# Power.net
KiCad netlist of a schematic drawn in Altium Designer
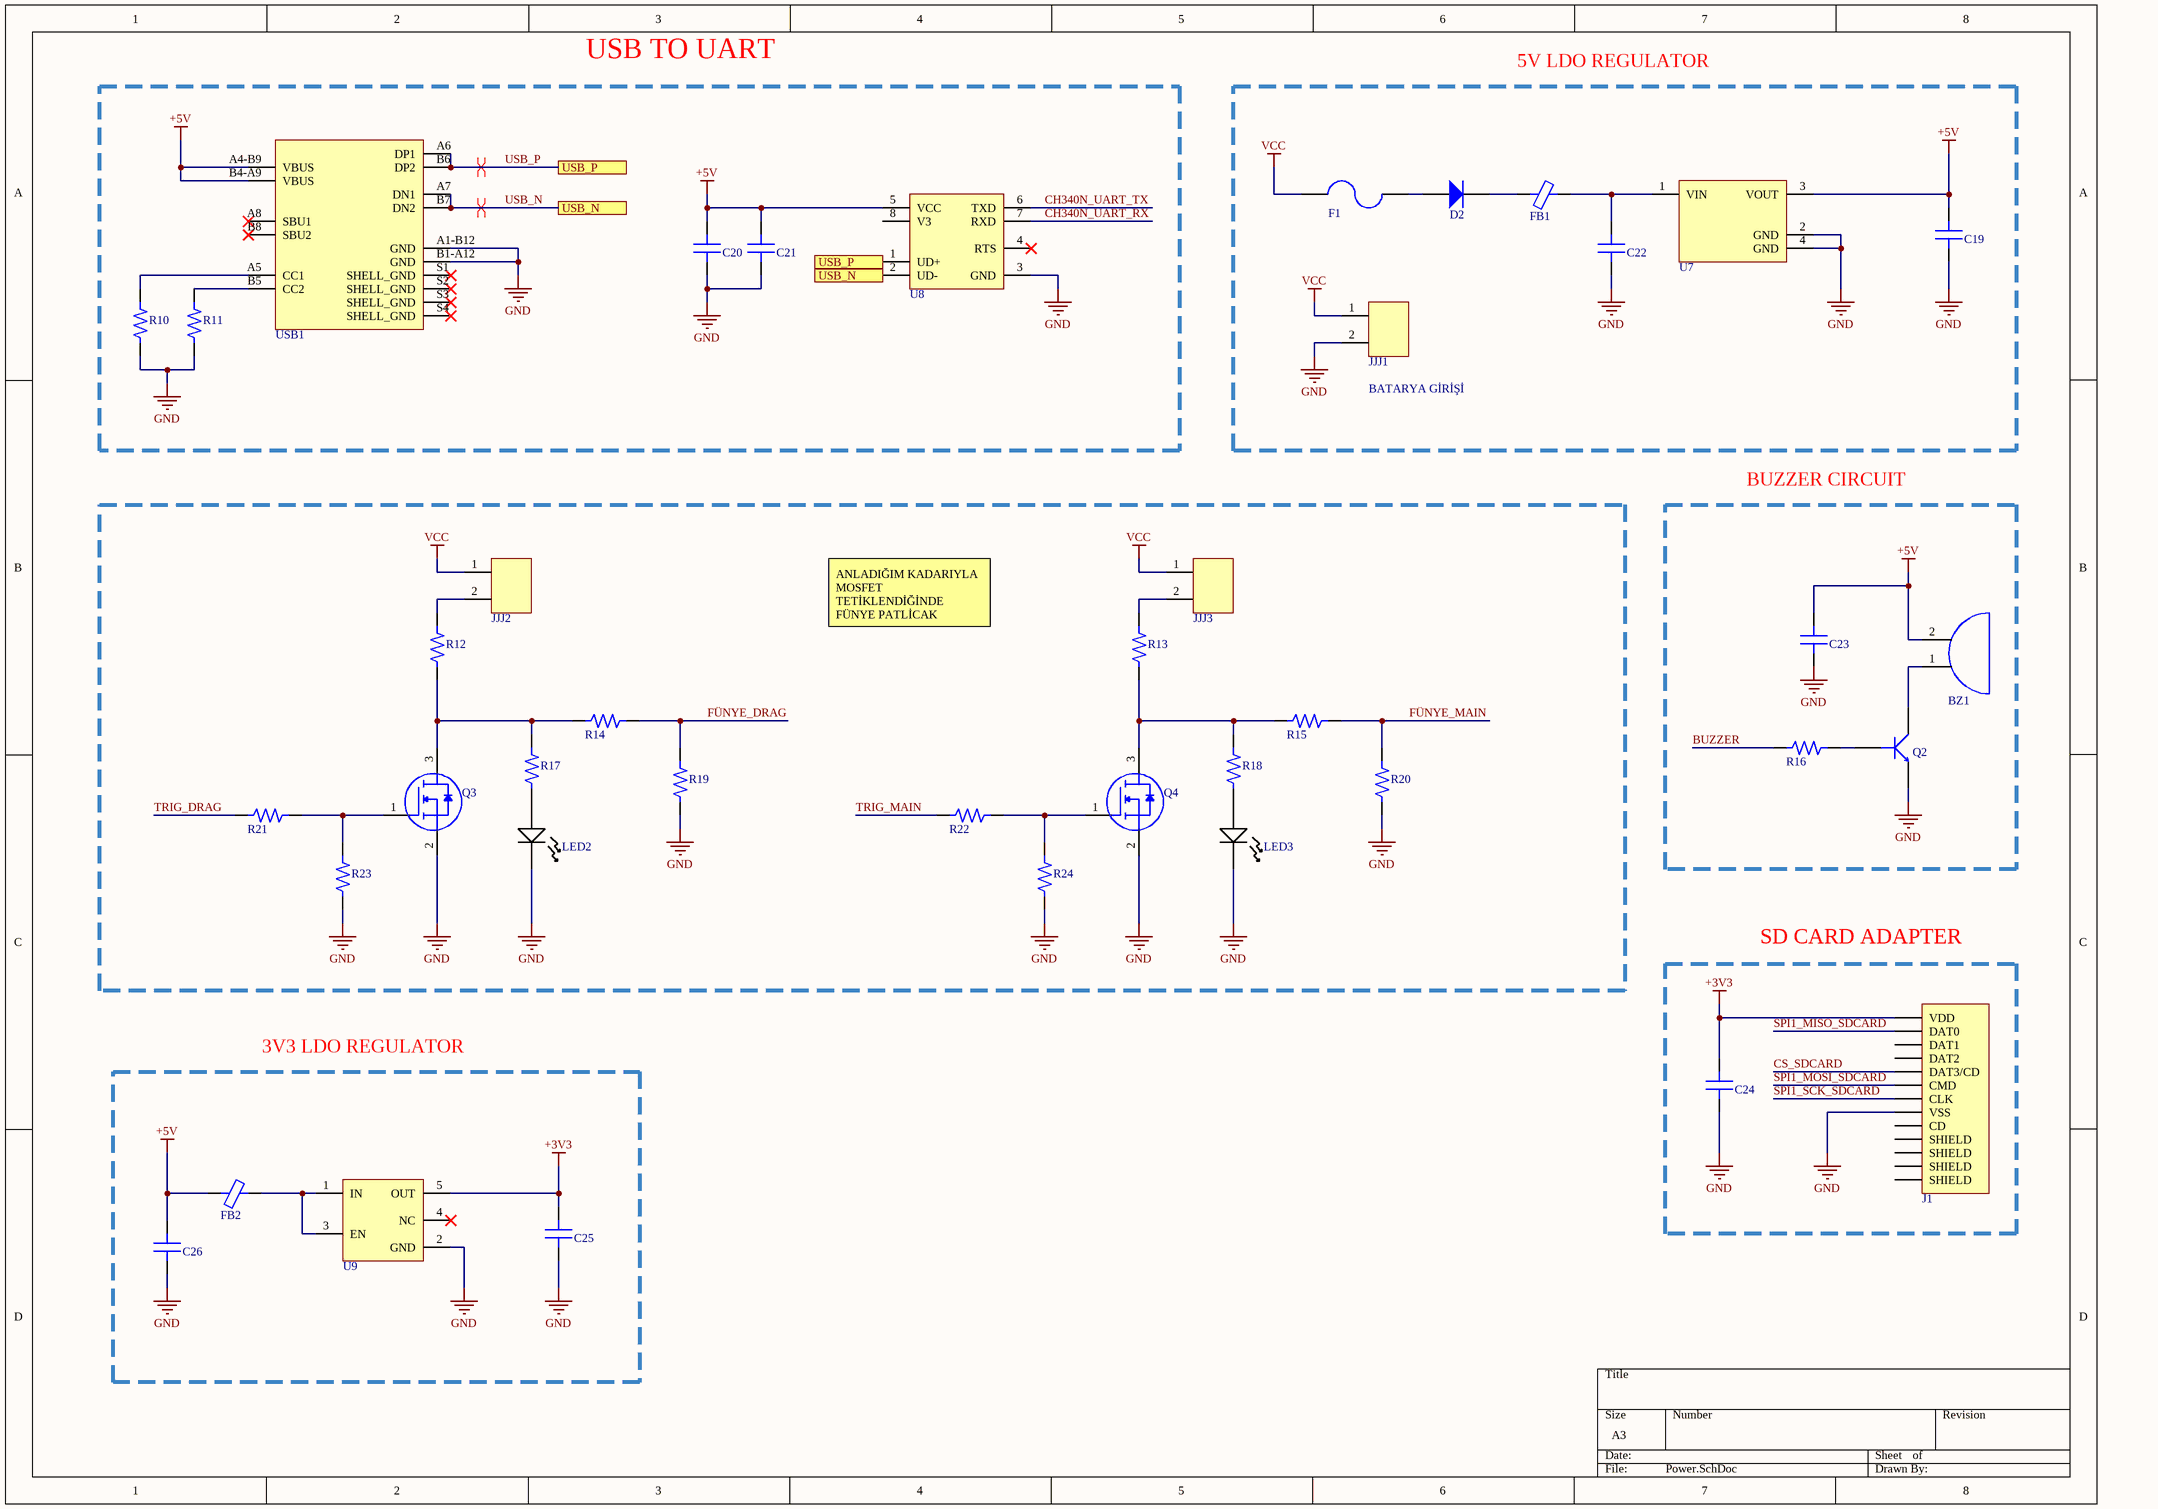
[diagram p0: Power.SchDoc]

(export (version "E")
  (design (tool "Eeschema 10.0.6"))
  (components
    (comp (ref "BZ1")
      (value "CMI-9605IC-0580T")
      (footprint "BUZZER")
      (description "Audio Buzzer Magnetic 3VDC 7VDC 30mA 5VDC 85dB 2600Hz to 2800Hz Through Hole Pin Box")
      (fields (field (name "MANUFACTURER") "CUI Devices"))
      (libsource (lib "ROKET_LIBRARY") (part "BUZZER"))
    )
    (comp (ref "C19")
      (value "CAP CER 10uF 0805")
      (footprint "CAP_0805")
      (libsource (lib "ROKET_LIBRARY") (part "CAP CER 10uF 0805"))
    )
    (comp (ref "C20")
      (value "CAP CER 100nF 0805")
      (footprint "CAP_0805")
      (libsource (lib "ROKET_LIBRARY") (part "CAP CER 100nF 0805"))
    )
    (comp (ref "C21")
      (value "CAP CER 100nF 0805")
      (footprint "CAP_0805")
      (libsource (lib "ROKET_LIBRARY") (part "CAP CER 100nF 0805"))
    )
    (comp (ref "C22")
      (value "CAP CER 10uF 0805")
      (footprint "CAP_0805")
      (libsource (lib "ROKET_LIBRARY") (part "CAP CER 10uF 0805"))
    )
    (comp (ref "C23")
      (value "CAP CER 100nF 0805")
      (footprint "CAP_0805")
      (libsource (lib "ROKET_LIBRARY") (part "CAP CER 100nF 0805"))
    )
    (comp (ref "C24")
      (value "CAP CER 100nF 0805")
      (footprint "CAP_0805")
      (libsource (lib "ROKET_LIBRARY") (part "CAP CER 100nF 0805"))
    )
    (comp (ref "C25")
      (value "CAP CER 1uF 0805")
      (footprint "CAP_0805")
      (libsource (lib "ROKET_LIBRARY") (part "CAP CER 1uF 0805"))
    )
    (comp (ref "C26")
      (value "CAP CER 1uF 0805")
      (footprint "CAP_0805")
      (libsource (lib "ROKET_LIBRARY") (part "CAP CER 1uF 0805"))
    )
    (comp (ref "D2")
      (value "DIODE GEN PURP 75V 150MA SOD323F")
      (footprint "SOD323F")
      (description "VR=75V IF=150mA Trr=4ns P=200mW")
      (fields
        (field (name "MANUFACTURER") "ON Semiconductor / Fairchild")
        (field (name "MANUFACTURER PART NUMBER") "1N4148WS")
      )
      (libsource (lib "ROKET_LIBRARY") (part "DIODE"))
    )
    (comp (ref "F1")
      (value "FUSE 3413.0216.22")
      (footprint "FUSE_1206")
      (description "Fuse Chip Fast Acting 1A 32V SMD Solder Pad 1206 Glass T/R VDE/cULus")
      (fields
        (field (name "MANUFACTURER") "Schurter")
        (field (name "MANUFACTURER PART NUMBER") "3413.0216.22")
      )
      (libsource (lib "ROKET_LIBRARY") (part "FUSE"))
    )
    (comp (ref "FB1")
      (value "MPZ2012S601AT000")
      (footprint "FERRITE BEAD_0805")
      (description "0805 600Ω ±25% DCR=0.1Ω 2A")
      (fields (field (name "MANUFACTURER") "TDK"))
      (libsource (lib "ROKET_LIBRARY") (part "FERRITE BEAD"))
    )
    (comp (ref "FB2")
      (value "MPZ2012S601AT000")
      (footprint "FERRITE BEAD_0805")
      (description "0805 600Ω ±25% DCR=0.1Ω 2A")
      (fields (field (name "MANUFACTURER") "TDK"))
      (libsource (lib "ROKET_LIBRARY") (part "FERRITE BEAD"))
    )
    (comp (ref "J1")
      (value "MEM2075-00-140-01-A")
      (footprint "SD CARD")
      (description "MEM2075 Series Normally Open SMT Push-Push MicroSD Memory Card Connector")
      (fields (field (name "MANUFACTURER") "Global Connector Technology"))
      (libsource (lib "ROKET_LIBRARY") (part "SD CARD"))
    )
    (comp (ref "JJJ1")
      (value "HEADER x2")
      (footprint "HEADER x2")
      (description "Conn Screw Type Terminal Block 2 POS 3.5mm Solder ST Thru-Hole 10A")
      (fields
        (field (name "MANUFACTURER") "On-Shore Technology")
        (field (name "MANUFACTURER PART NUMBER") "OSTTE020104")
      )
      (libsource (lib "Roket_Library") (part "HEADER x2"))
    )
    (comp (ref "JJJ2")
      (value "HEADER x2")
      (footprint "HEADER x2")
      (description "Conn Screw Type Terminal Block 2 POS 3.5mm Solder ST Thru-Hole 10A")
      (fields
        (field (name "MANUFACTURER") "On-Shore Technology")
        (field (name "MANUFACTURER PART NUMBER") "OSTTE020104")
      )
      (libsource (lib "Roket_Library") (part "HEADER x2"))
    )
    (comp (ref "JJJ3")
      (value "HEADER x2")
      (footprint "HEADER x2")
      (description "Conn Screw Type Terminal Block 2 POS 3.5mm Solder ST Thru-Hole 10A")
      (fields
        (field (name "MANUFACTURER") "On-Shore Technology")
        (field (name "MANUFACTURER PART NUMBER") "OSTTE020104")
      )
      (libsource (lib "Roket_Library") (part "HEADER x2"))
    )
    (comp (ref "LED2")
      (value "CMD17-21VRD/TR8")
      (footprint "LED RED_0805")
      (description "LED Uni-Color Red 640nm 2-Pin SMT T/R")
      (fields (field (name "MANUFACTURER") "VCC CHML"))
      (libsource (lib "ROKET_LIBRARY") (part "LED RED"))
    )
    (comp (ref "LED3")
      (value "CMD17-21VRD/TR8")
      (footprint "LED RED_0805")
      (description "LED Uni-Color Red 640nm 2-Pin SMT T/R")
      (fields (field (name "MANUFACTURER") "VCC CHML"))
      (libsource (lib "ROKET_LIBRARY") (part "LED RED"))
    )
    (comp (ref "Q2")
      (value "MMBT3904-7-F")
      (footprint "SOT_23F")
      (description "NPN Ic=200mA Vceo=40V hfe=100~300 fT=310MHz P=300mW SOT-23")
      (fields (field (name "MANUFACTURER") "Diodes Zetex"))
      (libsource (lib "ROKET_LIBRARY") (part "BJT_NPN"))
    )
    (comp (ref "Q3")
      (value "NTR5103NT1G")
      (footprint "SOT-23-3")
      (description "MOSFET N-CH 60V 0.26A SOT23")
      (fields (field (name "MANUFACTURER") "ON Semiconductor"))
      (libsource (lib "ROKET_LIBRARY") (part "MOSFET N-Channel"))
    )
    (comp (ref "Q4")
      (value "NTR5103NT1G")
      (footprint "SOT-23-3")
      (description "MOSFET N-CH 60V 0.26A SOT23")
      (fields (field (name "MANUFACTURER") "ON Semiconductor"))
      (libsource (lib "ROKET_LIBRARY") (part "MOSFET N-Channel"))
    )
    (comp (ref "R10")
      (value "RES 10K OHM 0805")
      (footprint "RES_0805")
      (libsource (lib "ROKET_LIBRARY") (part "RES 10K OHM 0805"))
    )
    (comp (ref "R11")
      (value "RES 10K OHM 0805")
      (footprint "RES_0805")
      (libsource (lib "ROKET_LIBRARY") (part "RES 10K OHM 0805"))
    )
    (comp (ref "R12")
      (value "RES 0 OHM 0805")
      (footprint "RES_0805")
      (libsource (lib "ROKET_LIBRARY") (part "RES 0 OHM 0805"))
    )
    (comp (ref "R13")
      (value "RES 0 OHM 0805")
      (footprint "RES_0805")
      (libsource (lib "ROKET_LIBRARY") (part "RES 0 OHM 0805"))
    )
    (comp (ref "R14")
      (value "RES 20K OHM 0805")
      (footprint "RES_0805")
      (libsource (lib "ROKET_LIBRARY") (part "RES 20K OHM 0805"))
    )
    (comp (ref "R15")
      (value "RES 20K OHM 0805")
      (footprint "RES_0805")
      (libsource (lib "ROKET_LIBRARY") (part "RES 20K OHM 0805"))
    )
    (comp (ref "R16")
      (value "RES 100 OHM 0805")
      (footprint "RES_0805")
      (libsource (lib "ROKET_LIBRARY") (part "RES 100 OHM 0805"))
    )
    (comp (ref "R17")
      (value "RES 470 OHM 0805")
      (footprint "RES_0805")
      (libsource (lib "ROKET_LIBRARY") (part "RES 470 OHM 0805"))
    )
    (comp (ref "R18")
      (value "RES 470 OHM 0805")
      (footprint "RES_0805")
      (libsource (lib "ROKET_LIBRARY") (part "RES 470 OHM 0805"))
    )
    (comp (ref "R19")
      (value "RES 10K OHM 0805")
      (footprint "RES_0805")
      (libsource (lib "ROKET_LIBRARY") (part "RES 10K OHM 0805"))
    )
    (comp (ref "R20")
      (value "RES 10K OHM 0805")
      (footprint "RES_0805")
      (libsource (lib "ROKET_LIBRARY") (part "RES 10K OHM 0805"))
    )
    (comp (ref "R21")
      (value "RES 1K OHM 0805")
      (footprint "RES_0805")
      (libsource (lib "ROKET_LIBRARY") (part "RES 1K OHM 0805"))
    )
    (comp (ref "R22")
      (value "RES 1K OHM 0805")
      (footprint "RES_0805")
      (libsource (lib "ROKET_LIBRARY") (part "RES 1K OHM 0805"))
    )
    (comp (ref "R23")
      (value "RES 10K OHM 0805")
      (footprint "RES_0805")
      (libsource (lib "ROKET_LIBRARY") (part "RES 10K OHM 0805"))
    )
    (comp (ref "R24")
      (value "RES 10K OHM 0805")
      (footprint "RES_0805")
      (libsource (lib "ROKET_LIBRARY") (part "RES 10K OHM 0805"))
    )
    (comp (ref "U7")
      (value "MCP1825S-5002E/DB")
      (footprint "SOT-223-3")
      (description "IC; Linear Regulator; Max. Input; 6V; Output; 5V; 500MA; Accuracy; 0.5%; SOT223-3")
      (fields (field (name "MANUFACTURER") "Microchip"))
      (libsource (lib "ROKET_LIBRARY") (part "MCP1825S-5002E/DB"))
    )
    (comp (ref "U8")
      (value "CH340N")
      (footprint "SOP-8")
      (description "USB TO UART TTL CONVERTER - SOP 8 PACKAGE")
      (libsource (lib "ROKET_LIBRARY") (part "CH340N"))
    )
    (comp (ref "U9")
      (value "NCP161ASN330T1G")
      (footprint "SOT-23-5")
      (description "LDO Regulator, 450 mA, Ultra-High PSRR, Ultra-Low Noise 3.3V, SOT23-5L, Active Discharge")
      (fields (field (name "MANUFACTURER") "ON Semiconductor"))
      (libsource (lib "ROKET_LIBRARY") (part "NCP161ASN330T1G"))
    )
    (comp (ref "USB1")
      (value "USB4125-GF-A")
      (footprint "USB4125-GF-A / Type C USB")
      (description "USB Connector with 1.90mm shell stake length")
      (fields
        (field (name "MANUFACTURER") "Global Connector Technology")
        (field (name "MANUFACTURER PART NUMBER") "USB4125-GF-A-0190")
      )
      (libsource (lib "ROKET_LIBRARY") (part "TYPE C USB CONNECTOR"))
    )
  )
  (nets
    (net (code "1") (name "+3V3") (class "Default")
      (node (ref "C24") (pin "2") (pinfunction "2_2") (pintype "passive"))
      (node (ref "C25") (pin "2") (pinfunction "2_2") (pintype "passive"))
      (node (ref "J1") (pin "P4") (pinfunction "VDD_P4") (pintype "passive"))
      (node (ref "U9") (pin "5") (pinfunction "OUT_5") (pintype "passive"))
    )
    (net (code "2") (name "+5V") (class "Default")
      (node (ref "BZ1") (pin "2") (pinfunction "2_2") (pintype "passive"))
      (node (ref "C19") (pin "2") (pinfunction "2_2") (pintype "passive"))
      (node (ref "C20") (pin "2") (pinfunction "2_2") (pintype "passive"))
      (node (ref "C21") (pin "2") (pinfunction "2_2") (pintype "passive"))
      (node (ref "C23") (pin "2") (pinfunction "2_2") (pintype "passive"))
      (node (ref "C26") (pin "2") (pinfunction "2_2") (pintype "passive"))
      (node (ref "FB2") (pin "1") (pinfunction "1_1") (pintype "passive"))
      (node (ref "U7") (pin "3") (pinfunction "VOUT_3") (pintype "passive"))
      (node (ref "U8") (pin "5") (pinfunction "VCC_5") (pintype "passive"))
      (node (ref "USB1") (pin "A4-B9") (pinfunction "VBUS_A4-B9") (pintype "passive"))
      (node (ref "USB1") (pin "B4-A9") (pinfunction "VBUS_B4-A9") (pintype "passive"))
    )
    (net (code "3") (name "/BUZZER") (class "Default")
      (node (ref "R16") (pin "1") (pinfunction "1_1") (pintype "passive"))
    )
    (net (code "4") (name "/CH340N_UART_RX") (class "Default")
      (node (ref "U8") (pin "7") (pinfunction "RXD_7") (pintype "passive"))
    )
    (net (code "5") (name "/CH340N_UART_TX") (class "Default")
      (node (ref "U8") (pin "6") (pinfunction "TXD_6") (pintype "passive"))
    )
    (net (code "6") (name "/CS_SDCARD") (class "Default")
      (node (ref "J1") (pin "P2") (pinfunction "DAT3/CD_P2") (pintype "passive"))
    )
    (net (code "7") (name "/FÜNYE_DRAG") (class "Default")
      (node (ref "R14") (pin "2") (pinfunction "2_2") (pintype "passive"))
      (node (ref "R19") (pin "2") (pinfunction "2_2") (pintype "passive"))
    )
    (net (code "8") (name "/FÜNYE_MAIN") (class "Default")
      (node (ref "R15") (pin "2") (pinfunction "2_2") (pintype "passive"))
      (node (ref "R20") (pin "2") (pinfunction "2_2") (pintype "passive"))
    )
    (net (code "9") (name "/SPI1_MISO_SDCARD") (class "Default")
      (node (ref "J1") (pin "P7") (pinfunction "DAT0_P7") (pintype "passive"))
    )
    (net (code "10") (name "/SPI1_MOSI_SDCARD") (class "Default")
      (node (ref "J1") (pin "P3") (pinfunction "CMD_P3") (pintype "passive"))
    )
    (net (code "11") (name "/SPI1_SCK_SDCARD") (class "Default")
      (node (ref "J1") (pin "P5") (pinfunction "CLK_P5") (pintype "passive"))
    )
    (net (code "12") (name "/TRIG_DRAG") (class "Default")
      (node (ref "R21") (pin "1") (pinfunction "1_1") (pintype "passive"))
    )
    (net (code "13") (name "/TRIG_MAIN") (class "Default")
      (node (ref "R22") (pin "1") (pinfunction "1_1") (pintype "passive"))
    )
    (net (code "14") (name "/USB_N") (class "Default")
      (node (ref "U8") (pin "2") (pinfunction "UD-_2") (pintype "passive"))
      (node (ref "USB1") (pin "A7") (pinfunction "DN1_A7") (pintype "passive"))
      (node (ref "USB1") (pin "B7") (pinfunction "DN2_B7") (pintype "passive"))
    )
    (net (code "15") (name "/USB_P") (class "Default")
      (node (ref "U8") (pin "1") (pinfunction "UD+_1") (pintype "passive"))
      (node (ref "USB1") (pin "A6") (pinfunction "DP1_A6") (pintype "passive"))
      (node (ref "USB1") (pin "B6") (pinfunction "DP2_B6") (pintype "passive"))
    )
    (net (code "16") (name "GND") (class "Default")
      (node (ref "C19") (pin "1") (pinfunction "1_1") (pintype "passive"))
      (node (ref "C20") (pin "1") (pinfunction "1_1") (pintype "passive"))
      (node (ref "C21") (pin "1") (pinfunction "1_1") (pintype "passive"))
      (node (ref "C22") (pin "1") (pinfunction "1_1") (pintype "passive"))
      (node (ref "C23") (pin "1") (pinfunction "1_1") (pintype "passive"))
      (node (ref "C24") (pin "1") (pinfunction "1_1") (pintype "passive"))
      (node (ref "C25") (pin "1") (pinfunction "1_1") (pintype "passive"))
      (node (ref "C26") (pin "1") (pinfunction "1_1") (pintype "passive"))
      (node (ref "J1") (pin "P6") (pinfunction "VSS_P6") (pintype "passive"))
      (node (ref "JJJ1") (pin "2") (pinfunction "2_2") (pintype "passive"))
      (node (ref "LED2") (pin "2") (pinfunction "2_2") (pintype "passive"))
      (node (ref "LED3") (pin "2") (pinfunction "2_2") (pintype "passive"))
      (node (ref "Q2") (pin "2") (pinfunction "E_2") (pintype "passive"))
      (node (ref "Q3") (pin "2") (pinfunction "S_2") (pintype "passive"))
      (node (ref "Q4") (pin "2") (pinfunction "S_2") (pintype "passive"))
      (node (ref "R10") (pin "1") (pinfunction "1_1") (pintype "passive"))
      (node (ref "R11") (pin "1") (pinfunction "1_1") (pintype "passive"))
      (node (ref "R19") (pin "1") (pinfunction "1_1") (pintype "passive"))
      (node (ref "R20") (pin "1") (pinfunction "1_1") (pintype "passive"))
      (node (ref "R23") (pin "1") (pinfunction "1_1") (pintype "passive"))
      (node (ref "R24") (pin "1") (pinfunction "1_1") (pintype "passive"))
      (node (ref "U7") (pin "2") (pinfunction "GND_2") (pintype "passive"))
      (node (ref "U7") (pin "4") (pinfunction "GND_4") (pintype "passive"))
      (node (ref "U8") (pin "3") (pinfunction "GND_3") (pintype "passive"))
      (node (ref "U9") (pin "2") (pinfunction "GND_2") (pintype "passive"))
      (node (ref "USB1") (pin "A1-B12") (pinfunction "GND_A1-B12") (pintype "passive"))
      (node (ref "USB1") (pin "B1-A12") (pinfunction "GND_B1-A12") (pintype "passive"))
    )
    (net (code "17") (name "Net-(D2-ANODE)") (class "Default")
      (node (ref "D2") (pin "2") (pinfunction "ANODE_2") (pintype "passive"))
      (node (ref "F1") (pin "2") (pinfunction "2_2") (pintype "passive"))
    )
    (net (code "18") (name "Net-(D2-CATHODE)") (class "Default")
      (node (ref "D2") (pin "1") (pinfunction "CATHODE_1") (pintype "passive"))
      (node (ref "FB1") (pin "1") (pinfunction "1_1") (pintype "passive"))
    )
    (net (code "19") (name "Net-(JJJ2-Pad2)") (class "Default")
      (node (ref "JJJ2") (pin "2") (pinfunction "2_2") (pintype "passive"))
      (node (ref "R12") (pin "2") (pinfunction "2_2") (pintype "passive"))
    )
    (net (code "20") (name "Net-(JJJ3-Pad2)") (class "Default")
      (node (ref "JJJ3") (pin "2") (pinfunction "2_2") (pintype "passive"))
      (node (ref "R13") (pin "2") (pinfunction "2_2") (pintype "passive"))
    )
    (net (code "21") (name "Net-(LED2-Pad1)") (class "Default")
      (node (ref "LED2") (pin "1") (pinfunction "1_1") (pintype "passive"))
      (node (ref "R17") (pin "1") (pinfunction "1_1") (pintype "passive"))
    )
    (net (code "22") (name "Net-(LED3-Pad1)") (class "Default")
      (node (ref "LED3") (pin "1") (pinfunction "1_1") (pintype "passive"))
      (node (ref "R18") (pin "1") (pinfunction "1_1") (pintype "passive"))
    )
    (net (code "23") (name "Net-(Q2-B)") (class "Default")
      (node (ref "Q2") (pin "1") (pinfunction "B_1") (pintype "passive"))
      (node (ref "R16") (pin "2") (pinfunction "2_2") (pintype "passive"))
    )
    (net (code "24") (name "Net-(Q2-C)") (class "Default")
      (node (ref "BZ1") (pin "1") (pinfunction "1_1") (pintype "passive"))
      (node (ref "Q2") (pin "3") (pinfunction "C_3") (pintype "passive"))
    )
    (net (code "25") (name "Net-(Q3-D)") (class "Default")
      (node (ref "Q3") (pin "3") (pinfunction "D_3") (pintype "passive"))
      (node (ref "R12") (pin "1") (pinfunction "1_1") (pintype "passive"))
      (node (ref "R14") (pin "1") (pinfunction "1_1") (pintype "passive"))
      (node (ref "R17") (pin "2") (pinfunction "2_2") (pintype "passive"))
    )
    (net (code "26") (name "Net-(Q3-G)") (class "Default")
      (node (ref "Q3") (pin "1") (pinfunction "G_1") (pintype "passive"))
      (node (ref "R21") (pin "2") (pinfunction "2_2") (pintype "passive"))
      (node (ref "R23") (pin "2") (pinfunction "2_2") (pintype "passive"))
    )
    (net (code "27") (name "Net-(Q4-D)") (class "Default")
      (node (ref "Q4") (pin "3") (pinfunction "D_3") (pintype "passive"))
      (node (ref "R13") (pin "1") (pinfunction "1_1") (pintype "passive"))
      (node (ref "R15") (pin "1") (pinfunction "1_1") (pintype "passive"))
      (node (ref "R18") (pin "2") (pinfunction "2_2") (pintype "passive"))
    )
    (net (code "28") (name "Net-(Q4-G)") (class "Default")
      (node (ref "Q4") (pin "1") (pinfunction "G_1") (pintype "passive"))
      (node (ref "R22") (pin "2") (pinfunction "2_2") (pintype "passive"))
      (node (ref "R24") (pin "2") (pinfunction "2_2") (pintype "passive"))
    )
    (net (code "29") (name "Net-(U7-VIN)") (class "Default")
      (node (ref "C22") (pin "2") (pinfunction "2_2") (pintype "passive"))
      (node (ref "FB1") (pin "2") (pinfunction "2_2") (pintype "passive"))
      (node (ref "U7") (pin "1") (pinfunction "VIN_1") (pintype "passive"))
    )
    (net (code "30") (name "Net-(U9-EN)") (class "Default")
      (node (ref "FB2") (pin "2") (pinfunction "2_2") (pintype "passive"))
      (node (ref "U9") (pin "1") (pinfunction "IN_1") (pintype "passive"))
      (node (ref "U9") (pin "3") (pinfunction "EN_3") (pintype "passive"))
    )
    (net (code "31") (name "Net-(USB1-CC1)") (class "Default")
      (node (ref "R10") (pin "2") (pinfunction "2_2") (pintype "passive"))
      (node (ref "USB1") (pin "A5") (pinfunction "CC1_A5") (pintype "passive"))
    )
    (net (code "32") (name "Net-(USB1-CC2)") (class "Default")
      (node (ref "R11") (pin "2") (pinfunction "2_2") (pintype "passive"))
      (node (ref "USB1") (pin "B5") (pinfunction "CC2_B5") (pintype "passive"))
    )
    (net (code "33") (name "VCC") (class "Default")
      (node (ref "F1") (pin "1") (pinfunction "1_1") (pintype "passive"))
      (node (ref "JJJ1") (pin "1") (pinfunction "1_1") (pintype "passive"))
      (node (ref "JJJ2") (pin "1") (pinfunction "1_1") (pintype "passive"))
      (node (ref "JJJ3") (pin "1") (pinfunction "1_1") (pintype "passive"))
    )
    (net (code "34") (name "unconnected-(J1-CD-PadP9)") (class "Default")
      (node (ref "J1") (pin "P9") (pinfunction "CD_P9") (pintype "passive"))
    )
    (net (code "35") (name "unconnected-(J1-DAT1-PadP8)") (class "Default")
      (node (ref "J1") (pin "P8") (pinfunction "DAT1_P8") (pintype "passive"))
    )
    (net (code "36") (name "unconnected-(J1-DAT2-PadP1)") (class "Default")
      (node (ref "J1") (pin "P1") (pinfunction "DAT2_P1") (pintype "passive"))
    )
    (net (code "37") (name "unconnected-(J1-SHIELD-PadSH1)") (class "Default")
      (node (ref "J1") (pin "SH1") (pinfunction "SHIELD_SH1") (pintype "passive"))
    )
    (net (code "38") (name "unconnected-(J1-SHIELD-PadSH2)") (class "Default")
      (node (ref "J1") (pin "SH2") (pinfunction "SHIELD_SH2") (pintype "passive"))
    )
    (net (code "39") (name "unconnected-(J1-SHIELD-PadSH3)") (class "Default")
      (node (ref "J1") (pin "SH3") (pinfunction "SHIELD_SH3") (pintype "passive"))
    )
    (net (code "40") (name "unconnected-(J1-SHIELD-PadSH4)") (class "Default")
      (node (ref "J1") (pin "SH4") (pinfunction "SHIELD_SH4") (pintype "passive"))
    )
    (net (code "41") (name "unconnected-(U8-RTS-Pad4)") (class "Default")
      (node (ref "U8") (pin "4") (pinfunction "RTS_4") (pintype "passive+no_connect"))
    )
    (net (code "42") (name "unconnected-(U8-V3-Pad8)") (class "Default")
      (node (ref "U8") (pin "8") (pinfunction "V3_8") (pintype "passive"))
    )
    (net (code "43") (name "unconnected-(U9-NC-Pad4)") (class "Default")
      (node (ref "U9") (pin "4") (pinfunction "NC_4") (pintype "passive+no_connect"))
    )
    (net (code "44") (name "unconnected-(USB1-SBU1-PadA8)") (class "Default")
      (node (ref "USB1") (pin "A8") (pinfunction "SBU1_A8") (pintype "passive+no_connect"))
    )
    (net (code "45") (name "unconnected-(USB1-SBU2-PadB8)") (class "Default")
      (node (ref "USB1") (pin "B8") (pinfunction "SBU2_B8") (pintype "passive+no_connect"))
    )
    (net (code "46") (name "unconnected-(USB1-SHELL_GND-PadS1)") (class "Default")
      (node (ref "USB1") (pin "S1") (pinfunction "SHELL_GND_S1") (pintype "passive+no_connect"))
    )
    (net (code "47") (name "unconnected-(USB1-SHELL_GND-PadS2)") (class "Default")
      (node (ref "USB1") (pin "S2") (pinfunction "SHELL_GND_S2") (pintype "passive+no_connect"))
    )
    (net (code "48") (name "unconnected-(USB1-SHELL_GND-PadS3)") (class "Default")
      (node (ref "USB1") (pin "S3") (pinfunction "SHELL_GND_S3") (pintype "passive+no_connect"))
    )
    (net (code "49") (name "unconnected-(USB1-SHELL_GND-PadS4)") (class "Default")
      (node (ref "USB1") (pin "S4") (pinfunction "SHELL_GND_S4") (pintype "passive+no_connect"))
    )
  )
)
